# ESP32C3_BUTTON_LED_WS2812B_Sheet.net
KiCad netlist of a schematic drawn in Altium Designer
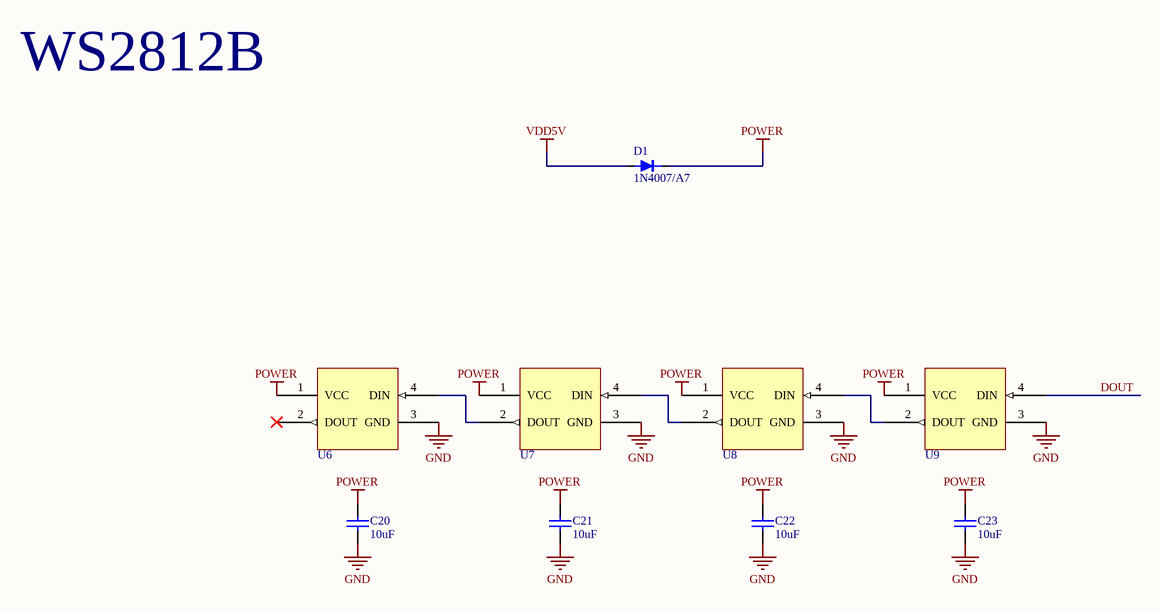
[diagram p0: ESP32C3_BUTTON_LED_WS2812B_Sheet.SchDoc]

(export (version "E")
  (design (tool "Eeschema 10.0.6"))
  (components
    (comp (ref "C20")
      (value "10uF")
      (footprint "0603")
      (description "Capacitor")
      (fields (field (name "Comment") "Cap") (field (name "PUBLISHER") "Altium Limited"))
      (libsource (lib "CORE_COMPONENT") (part "Cap"))
    )
    (comp (ref "C21")
      (value "10uF")
      (footprint "0603")
      (description "Capacitor")
      (fields (field (name "Comment") "Cap") (field (name "PUBLISHER") "Altium Limited"))
      (libsource (lib "CORE_COMPONENT") (part "Cap"))
    )
    (comp (ref "C22")
      (value "10uF")
      (footprint "0603")
      (description "Capacitor")
      (fields (field (name "Comment") "Cap") (field (name "PUBLISHER") "Altium Limited"))
      (libsource (lib "CORE_COMPONENT") (part "Cap"))
    )
    (comp (ref "C23")
      (value "10uF")
      (footprint "0603")
      (description "Capacitor")
      (fields (field (name "Comment") "Cap") (field (name "PUBLISHER") "Altium Limited"))
      (libsource (lib "CORE_COMPONENT") (part "Cap"))
    )
    (comp (ref "D1")
      (value "1N4007/A7")
      (footprint "SOD-123FL")
      (libsource (lib "CORE_COMPONENT") (part "DIODE"))
    )
    (comp (ref "U6") (value "WS2812B") (footprint "5050") (libsource (lib "CORE_COMPONENT") (part "WS2812B")))
    (comp (ref "U7") (value "WS2812B") (footprint "5050") (libsource (lib "CORE_COMPONENT") (part "WS2812B")))
    (comp (ref "U8") (value "WS2812B") (footprint "5050") (libsource (lib "CORE_COMPONENT") (part "WS2812B")))
    (comp (ref "U9") (value "WS2812B") (footprint "5050") (libsource (lib "CORE_COMPONENT") (part "WS2812B")))
  )
  (nets
    (net (code "1") (name "/DOUT") (class "Default")
      (node (ref "U9") (pin "4") (pinfunction "DIN_4") (pintype "input"))
    )
    (net (code "2") (name "GND") (class "Default")
      (node (ref "C20") (pin "2") (pinfunction "2_2") (pintype "passive"))
      (node (ref "C21") (pin "2") (pinfunction "2_2") (pintype "passive"))
      (node (ref "C22") (pin "2") (pinfunction "2_2") (pintype "passive"))
      (node (ref "C23") (pin "2") (pinfunction "2_2") (pintype "passive"))
      (node (ref "U6") (pin "3") (pinfunction "GND_3") (pintype "power_in"))
      (node (ref "U7") (pin "3") (pinfunction "GND_3") (pintype "power_in"))
      (node (ref "U8") (pin "3") (pinfunction "GND_3") (pintype "power_in"))
      (node (ref "U9") (pin "3") (pinfunction "GND_3") (pintype "power_in"))
    )
    (net (code "3") (name "Net-(U6-DIN)") (class "Default")
      (node (ref "U6") (pin "4") (pinfunction "DIN_4") (pintype "input"))
      (node (ref "U7") (pin "2") (pinfunction "DOUT_2") (pintype "output"))
    )
    (net (code "4") (name "Net-(U7-DIN)") (class "Default")
      (node (ref "U7") (pin "4") (pinfunction "DIN_4") (pintype "input"))
      (node (ref "U8") (pin "2") (pinfunction "DOUT_2") (pintype "output"))
    )
    (net (code "5") (name "Net-(U8-DIN)") (class "Default")
      (node (ref "U8") (pin "4") (pinfunction "DIN_4") (pintype "input"))
      (node (ref "U9") (pin "2") (pinfunction "DOUT_2") (pintype "output"))
    )
    (net (code "6") (name "POWER") (class "Default")
      (node (ref "C20") (pin "1") (pinfunction "1_1") (pintype "passive"))
      (node (ref "C21") (pin "1") (pinfunction "1_1") (pintype "passive"))
      (node (ref "C22") (pin "1") (pinfunction "1_1") (pintype "passive"))
      (node (ref "C23") (pin "1") (pinfunction "1_1") (pintype "passive"))
      (node (ref "D1") (pin "K") (pinfunction "K_K") (pintype "passive"))
      (node (ref "U6") (pin "1") (pinfunction "VCC_1") (pintype "power_in"))
      (node (ref "U7") (pin "1") (pinfunction "VCC_1") (pintype "power_in"))
      (node (ref "U8") (pin "1") (pinfunction "VCC_1") (pintype "power_in"))
      (node (ref "U9") (pin "1") (pinfunction "VCC_1") (pintype "power_in"))
    )
    (net (code "7") (name "VDD5V") (class "Default")
      (node (ref "D1") (pin "A") (pinfunction "A_A") (pintype "passive"))
    )
    (net (code "8") (name "unconnected-(U6-DOUT-Pad2)") (class "Default")
      (node (ref "U6") (pin "2") (pinfunction "DOUT_2") (pintype "output+no_connect"))
    )
  )
)
